# cafereg2.net
KiCad netlist of a schematic drawn in EAGLE
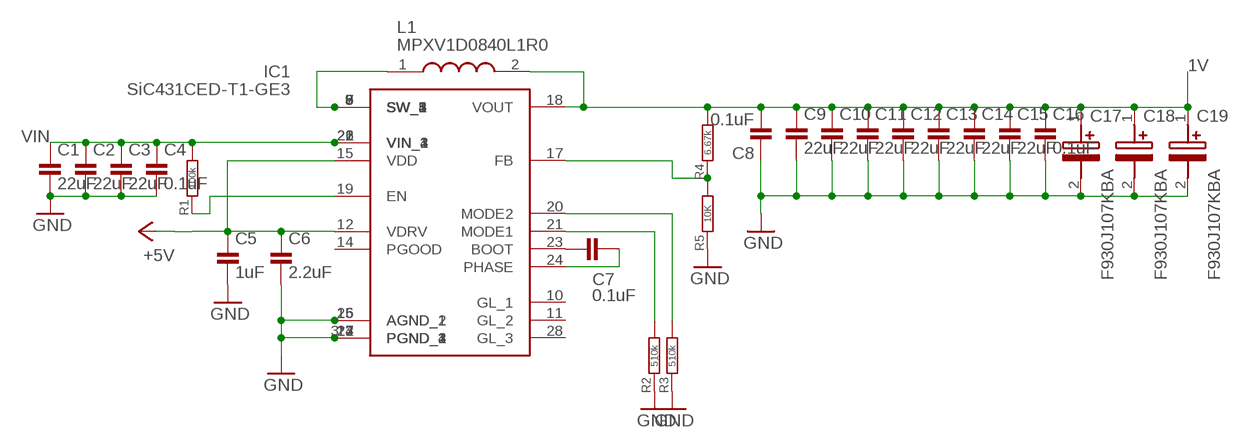
[diagram p0: schematic, sheet 1]
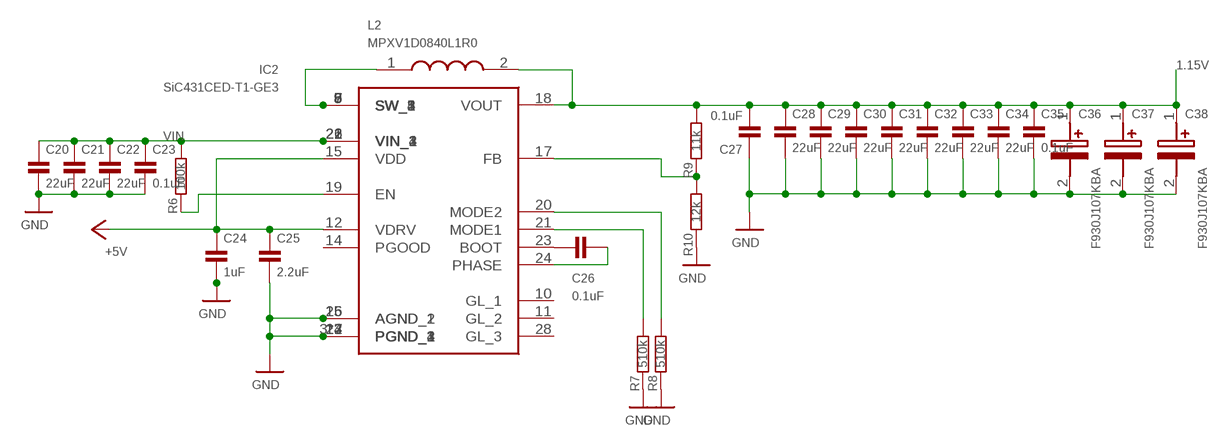
[diagram p1: schematic, sheet 2]
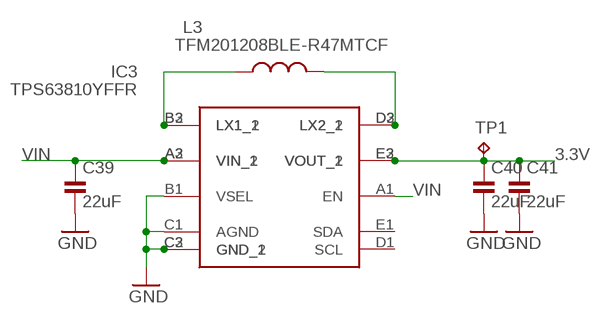
[diagram p2: schematic, sheet 3]
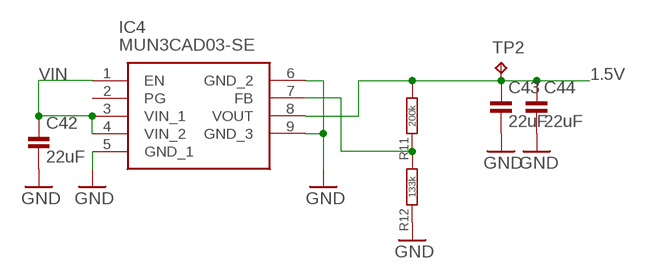
[diagram p3: schematic, sheet 4]
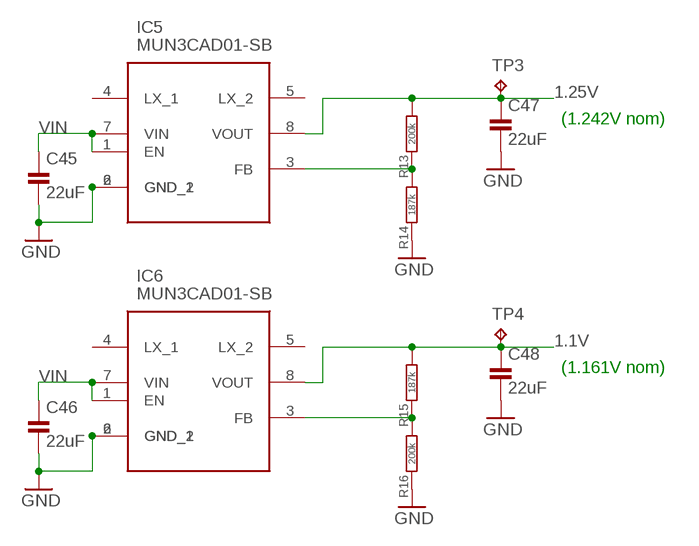
[diagram p4: schematic, sheet 5]
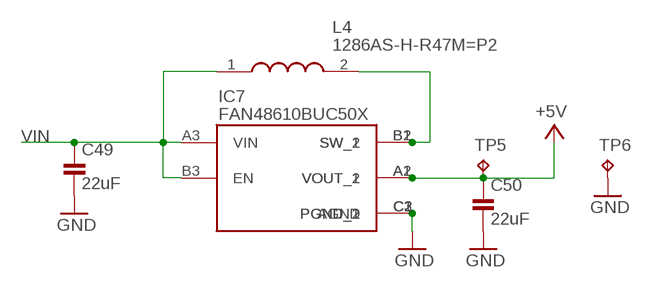
[diagram p5: schematic, sheet 6]

(export (version "E")
  (design (tool "Eeschema 10.0.6"))
  (components
    (comp (ref "C1")
      (value "22uF")
      (footprint "eagle-import:C0603")
      (libsource (lib "eagle-import") (part "C-USC0603"))
    )
    (comp (ref "C2")
      (value "22uF")
      (footprint "eagle-import:C0603")
      (libsource (lib "eagle-import") (part "C-USC0603"))
    )
    (comp (ref "C3")
      (value "22uF")
      (footprint "eagle-import:C0603")
      (libsource (lib "eagle-import") (part "C-USC0603"))
    )
    (comp (ref "C4")
      (value "0.1uF")
      (footprint "eagle-import:C0402")
      (libsource (lib "eagle-import") (part "C-USC0402"))
    )
    (comp (ref "C5")
      (value "1uF")
      (footprint "eagle-import:C0402")
      (libsource (lib "eagle-import") (part "C-USC0402"))
    )
    (comp (ref "C6")
      (value "2.2uF")
      (footprint "eagle-import:C0402")
      (libsource (lib "eagle-import") (part "C-USC0402"))
    )
    (comp (ref "C7")
      (value "0.1uF")
      (footprint "eagle-import:C0402")
      (libsource (lib "eagle-import") (part "C-USC0402"))
    )
    (comp (ref "C8")
      (value "0.1uF")
      (footprint "eagle-import:C0402")
      (libsource (lib "eagle-import") (part "C-USC0402"))
    )
    (comp (ref "C9")
      (value "22uF")
      (footprint "eagle-import:C0603")
      (libsource (lib "eagle-import") (part "C-USC0603"))
    )
    (comp (ref "C10")
      (value "22uF")
      (footprint "eagle-import:C0603")
      (libsource (lib "eagle-import") (part "C-USC0603"))
    )
    (comp (ref "C11")
      (value "22uF")
      (footprint "eagle-import:C0603")
      (libsource (lib "eagle-import") (part "C-USC0603"))
    )
    (comp (ref "C12")
      (value "22uF")
      (footprint "eagle-import:C0603")
      (libsource (lib "eagle-import") (part "C-USC0603"))
    )
    (comp (ref "C13")
      (value "22uF")
      (footprint "eagle-import:C0603")
      (libsource (lib "eagle-import") (part "C-USC0603"))
    )
    (comp (ref "C14")
      (value "22uF")
      (footprint "eagle-import:C0603")
      (libsource (lib "eagle-import") (part "C-USC0603"))
    )
    (comp (ref "C15")
      (value "22uF")
      (footprint "eagle-import:C0603")
      (libsource (lib "eagle-import") (part "C-USC0603"))
    )
    (comp (ref "C16")
      (value "0.1uF")
      (footprint "eagle-import:C0402")
      (libsource (lib "eagle-import") (part "C-USC0402"))
    )
    (comp (ref "C17")
      (value "F930J107KBA")
      (footprint "eagle-import:CAPPM3528X210N")
      (fields (field (name "MOUSER_PART_NUMBER") "647-F930J107KBA"))
      (libsource (lib "eagle-import") (part "F930J107KBA"))
    )
    (comp (ref "C18")
      (value "F930J107KBA")
      (footprint "eagle-import:CAPPM3528X210N")
      (fields (field (name "MOUSER_PART_NUMBER") "647-F930J107KBA"))
      (libsource (lib "eagle-import") (part "F930J107KBA"))
    )
    (comp (ref "C19")
      (value "F930J107KBA")
      (footprint "eagle-import:CAPPM3528X210N")
      (fields (field (name "MOUSER_PART_NUMBER") "647-F930J107KBA"))
      (libsource (lib "eagle-import") (part "F930J107KBA"))
    )
    (comp (ref "IC1")
      (value "SiC431CED-T1-GE3")
      (footprint "eagle-import:SIC431AEDT1GE3")
      (fields
        (field (name "MANUFACTURER_PART_NUMBER") "SiC431AED-T1-GE3")
        (field (name "MOUSER_PART_NUMBER") "78-SIC431AED-T1-GE3")
      )
      (libsource (lib "eagle-import") (part "SIC431AED-T1-GE3"))
    )
    (comp (ref "L1")
      (value "MPXV1D0840L1R0")
      (footprint "eagle-import:INDPM8680X400N")
      (libsource (lib "eagle-import") (part "MPXV1D0840L1R0"))
    )
    (comp (ref "R1")
      (value "100k")
      (footprint "eagle-import:R0402")
      (libsource (lib "eagle-import") (part "R-US_R0402"))
    )
    (comp (ref "R2")
      (value "510k")
      (footprint "eagle-import:R0402")
      (libsource (lib "eagle-import") (part "R-US_R0402"))
    )
    (comp (ref "R3")
      (value "510k")
      (footprint "eagle-import:R0402")
      (libsource (lib "eagle-import") (part "R-US_R0402"))
    )
    (comp (ref "R4")
      (value "6.67k")
      (footprint "eagle-import:R0402")
      (libsource (lib "eagle-import") (part "R-US_R0402"))
    )
    (comp (ref "R5")
      (value "10K")
      (footprint "eagle-import:R0402")
      (libsource (lib "eagle-import") (part "R-US_R0402"))
    )
    (comp (ref "C42")
      (value "22uF")
      (footprint "eagle-import:C0603")
      (libsource (lib "eagle-import") (part "C-USC0603"))
    )
    (comp (ref "C43")
      (value "22uF")
      (footprint "eagle-import:C0603")
      (libsource (lib "eagle-import") (part "C-USC0603"))
    )
    (comp (ref "C44")
      (value "22uF")
      (footprint "eagle-import:C0603")
      (libsource (lib "eagle-import") (part "C-USC0603"))
    )
    (comp (ref "IC4")
      (value "MUN3CAD03-SE")
      (footprint "eagle-import:MUN3CAD03SE")
      (fields (field (name "MOUSER_PART_NUMBER") "108-MUN3CAD03-SE"))
      (libsource (lib "eagle-import") (part "MUN3CAD03-SE"))
    )
    (comp (ref "R11")
      (value "200k")
      (footprint "eagle-import:R0402")
      (libsource (lib "eagle-import") (part "R-US_R0402"))
    )
    (comp (ref "R12")
      (value "133k")
      (footprint "eagle-import:R0402")
      (libsource (lib "eagle-import") (part "R-US_R0402"))
    )
    (comp (ref "TP2")
      (value "TPTP12SQ")
      (footprint "eagle-import:TP12SQ")
      (libsource (lib "eagle-import") (part "TPTP12SQ"))
    )
    (comp (ref "C49")
      (value "22uF")
      (footprint "eagle-import:C0603")
      (libsource (lib "eagle-import") (part "C-USC0603"))
    )
    (comp (ref "C50")
      (value "22uF")
      (footprint "eagle-import:C0603")
      (libsource (lib "eagle-import") (part "C-USC0603"))
    )
    (comp (ref "IC7")
      (value "FAN48610BUC50X")
      (footprint "eagle-import:BGA9C40P3X3_122X122X62")
      (fields (field (name "MOUSER_PART_NUMBER") "512-FAN48610BUC50X"))
      (libsource (lib "eagle-import") (part "FAN48610BUC50X"))
    )
    (comp (ref "L4")
      (value "1286AS-H-R47M=P2")
      (footprint "eagle-import:1286ASH1R0MP2")
      (fields (field (name "MOUSER_PART_NUMBER") "81-1286AS-H-R47MP2"))
      (libsource (lib "eagle-import") (part "1286AS-H-R47M=P2"))
    )
    (comp (ref "TP5")
      (value "TPTP12SQ")
      (footprint "eagle-import:TP12SQ")
      (libsource (lib "eagle-import") (part "TPTP12SQ"))
    )
    (comp (ref "TP6")
      (value "TPTP12SQ")
      (footprint "eagle-import:TP12SQ")
      (libsource (lib "eagle-import") (part "TPTP12SQ"))
    )
    (comp (ref "C45")
      (value "22uF")
      (footprint "eagle-import:C0603")
      (libsource (lib "eagle-import") (part "C-USC0603"))
    )
    (comp (ref "C46")
      (value "22uF")
      (footprint "eagle-import:C0603")
      (libsource (lib "eagle-import") (part "C-USC0603"))
    )
    (comp (ref "C47")
      (value "22uF")
      (footprint "eagle-import:C0603")
      (libsource (lib "eagle-import") (part "C-USC0603"))
    )
    (comp (ref "C48")
      (value "22uF")
      (footprint "eagle-import:C0603")
      (libsource (lib "eagle-import") (part "C-USC0603"))
    )
    (comp (ref "IC5")
      (value "MUN3CAD01-SB")
      (footprint "eagle-import:MUN3CAD01SB")
      (libsource (lib "eagle-import") (part "MUN3CAD01-SB"))
    )
    (comp (ref "IC6")
      (value "MUN3CAD01-SB")
      (footprint "eagle-import:MUN3CAD01SB")
      (libsource (lib "eagle-import") (part "MUN3CAD01-SB"))
    )
    (comp (ref "R13")
      (value "200k")
      (footprint "eagle-import:R0402")
      (libsource (lib "eagle-import") (part "R-US_R0402"))
    )
    (comp (ref "R14")
      (value "187k")
      (footprint "eagle-import:R0402")
      (libsource (lib "eagle-import") (part "R-US_R0402"))
    )
    (comp (ref "R15")
      (value "187k")
      (footprint "eagle-import:R0402")
      (libsource (lib "eagle-import") (part "R-US_R0402"))
    )
    (comp (ref "R16")
      (value "200k")
      (footprint "eagle-import:R0402")
      (libsource (lib "eagle-import") (part "R-US_R0402"))
    )
    (comp (ref "TP3")
      (value "TPTP12SQ")
      (footprint "eagle-import:TP12SQ")
      (libsource (lib "eagle-import") (part "TPTP12SQ"))
    )
    (comp (ref "TP4")
      (value "TPTP12SQ")
      (footprint "eagle-import:TP12SQ")
      (libsource (lib "eagle-import") (part "TPTP12SQ"))
    )
    (comp (ref "C20")
      (value "22uF")
      (footprint "eagle-import:C0603")
      (libsource (lib "eagle-import") (part "C-USC0603"))
    )
    (comp (ref "C21")
      (value "22uF")
      (footprint "eagle-import:C0603")
      (libsource (lib "eagle-import") (part "C-USC0603"))
    )
    (comp (ref "C22")
      (value "22uF")
      (footprint "eagle-import:C0603")
      (libsource (lib "eagle-import") (part "C-USC0603"))
    )
    (comp (ref "C23")
      (value "0.1uF")
      (footprint "eagle-import:C0402")
      (libsource (lib "eagle-import") (part "C-USC0402"))
    )
    (comp (ref "C24")
      (value "1uF")
      (footprint "eagle-import:C0402")
      (libsource (lib "eagle-import") (part "C-USC0402"))
    )
    (comp (ref "C25")
      (value "2.2uF")
      (footprint "eagle-import:C0402")
      (libsource (lib "eagle-import") (part "C-USC0402"))
    )
    (comp (ref "C26")
      (value "0.1uF")
      (footprint "eagle-import:C0402")
      (libsource (lib "eagle-import") (part "C-USC0402"))
    )
    (comp (ref "C27")
      (value "0.1uF")
      (footprint "eagle-import:C0402")
      (libsource (lib "eagle-import") (part "C-USC0402"))
    )
    (comp (ref "C28")
      (value "22uF")
      (footprint "eagle-import:C0603")
      (libsource (lib "eagle-import") (part "C-USC0603"))
    )
    (comp (ref "C29")
      (value "22uF")
      (footprint "eagle-import:C0603")
      (libsource (lib "eagle-import") (part "C-USC0603"))
    )
    (comp (ref "C30")
      (value "22uF")
      (footprint "eagle-import:C0603")
      (libsource (lib "eagle-import") (part "C-USC0603"))
    )
    (comp (ref "C31")
      (value "22uF")
      (footprint "eagle-import:C0603")
      (libsource (lib "eagle-import") (part "C-USC0603"))
    )
    (comp (ref "C32")
      (value "22uF")
      (footprint "eagle-import:C0603")
      (libsource (lib "eagle-import") (part "C-USC0603"))
    )
    (comp (ref "C33")
      (value "22uF")
      (footprint "eagle-import:C0603")
      (libsource (lib "eagle-import") (part "C-USC0603"))
    )
    (comp (ref "C34")
      (value "22uF")
      (footprint "eagle-import:C0603")
      (libsource (lib "eagle-import") (part "C-USC0603"))
    )
    (comp (ref "C35")
      (value "0.1uF")
      (footprint "eagle-import:C0402")
      (libsource (lib "eagle-import") (part "C-USC0402"))
    )
    (comp (ref "C36")
      (value "F930J107KBA")
      (footprint "eagle-import:CAPPM3528X210N")
      (fields (field (name "MOUSER_PART_NUMBER") "647-F930J107KBA"))
      (libsource (lib "eagle-import") (part "F930J107KBA"))
    )
    (comp (ref "C37")
      (value "F930J107KBA")
      (footprint "eagle-import:CAPPM3528X210N")
      (fields (field (name "MOUSER_PART_NUMBER") "647-F930J107KBA"))
      (libsource (lib "eagle-import") (part "F930J107KBA"))
    )
    (comp (ref "C38")
      (value "F930J107KBA")
      (footprint "eagle-import:CAPPM3528X210N")
      (fields (field (name "MOUSER_PART_NUMBER") "647-F930J107KBA"))
      (libsource (lib "eagle-import") (part "F930J107KBA"))
    )
    (comp (ref "IC2")
      (value "SiC431CED-T1-GE3")
      (footprint "eagle-import:SIC431AEDT1GE3")
      (fields
        (field (name "MANUFACTURER_PART_NUMBER") "SiC431AED-T1-GE3")
        (field (name "MOUSER_PART_NUMBER") "78-SIC431AED-T1-GE3")
      )
      (libsource (lib "eagle-import") (part "SIC431AED-T1-GE3"))
    )
    (comp (ref "L2")
      (value "MPXV1D0840L1R0")
      (footprint "eagle-import:INDPM8680X400N")
      (libsource (lib "eagle-import") (part "MPXV1D0840L1R0"))
    )
    (comp (ref "R6")
      (value "100k")
      (footprint "eagle-import:R0402")
      (libsource (lib "eagle-import") (part "R-US_R0402"))
    )
    (comp (ref "R7")
      (value "510k")
      (footprint "eagle-import:R0402")
      (libsource (lib "eagle-import") (part "R-US_R0402"))
    )
    (comp (ref "R8")
      (value "510k")
      (footprint "eagle-import:R0402")
      (libsource (lib "eagle-import") (part "R-US_R0402"))
    )
    (comp (ref "R9")
      (value "11k")
      (footprint "eagle-import:R0402")
      (libsource (lib "eagle-import") (part "R-US_R0402"))
    )
    (comp (ref "R10")
      (value "12k")
      (footprint "eagle-import:R0402")
      (libsource (lib "eagle-import") (part "R-US_R0402"))
    )
    (comp (ref "C39")
      (value "22uF")
      (footprint "eagle-import:C0603")
      (libsource (lib "eagle-import") (part "C-USC0603"))
    )
    (comp (ref "C40")
      (value "22uF")
      (footprint "eagle-import:C0603")
      (libsource (lib "eagle-import") (part "C-USC0603"))
    )
    (comp (ref "C41")
      (value "22uF")
      (footprint "eagle-import:C0603")
      (libsource (lib "eagle-import") (part "C-USC0603"))
    )
    (comp (ref "IC3")
      (value "TPS63810YFFR")
      (footprint "eagle-import:BGA15C40P3X5_134X226X62")
      (fields (field (name "MOUSER_PART_NUMBER") "595-TPS63810YFFR"))
      (libsource (lib "eagle-import") (part "TPS63810YFFR"))
    )
    (comp (ref "L3")
      (value "TFM201208BLE-R47MTCF")
      (footprint "eagle-import:INDC2009X120")
      (libsource (lib "eagle-import") (part "LCHIP-0805(2012-METRIC)_"))
    )
    (comp (ref "TP1")
      (value "TPTP12SQ")
      (footprint "eagle-import:TP12SQ")
      (libsource (lib "eagle-import") (part "TPTP12SQ"))
    )
  )
  (nets
    (net (code "1") (name "+5V") (class "Default")
      (node (ref "C24") (pin "1") (pinfunction "1_1") (pintype "passive"))
      (node (ref "C25") (pin "1") (pinfunction "1_1") (pintype "passive"))
      (node (ref "C5") (pin "1") (pinfunction "1_1") (pintype "passive"))
      (node (ref "C50") (pin "1") (pinfunction "1_1") (pintype "passive"))
      (node (ref "C6") (pin "1") (pinfunction "1_1") (pintype "passive"))
      (node (ref "IC1") (pin "12") (pinfunction "VDRV_12") (pintype "bidirectional"))
      (node (ref "IC1") (pin "15") (pinfunction "VDD_15") (pintype "bidirectional"))
      (node (ref "IC2") (pin "12") (pinfunction "VDRV_12") (pintype "bidirectional"))
      (node (ref "IC2") (pin "15") (pinfunction "VDD_15") (pintype "bidirectional"))
      (node (ref "IC7") (pin "A1") (pinfunction "VOUT_1_A1") (pintype "bidirectional"))
      (node (ref "IC7") (pin "A2") (pinfunction "VOUT_2_A2") (pintype "bidirectional"))
      (node (ref "TP5") (pin "TP") (pinfunction "TP_TP") (pintype "input"))
    )
    (net (code "2") (name "1.1V") (class "Default")
      (node (ref "C48") (pin "1") (pinfunction "1_1") (pintype "passive"))
      (node (ref "IC6") (pin "8") (pinfunction "VOUT_8") (pintype "bidirectional"))
      (node (ref "R15") (pin "2") (pinfunction "2_2") (pintype "passive"))
      (node (ref "TP4") (pin "TP") (pinfunction "TP_TP") (pintype "input"))
    )
    (net (code "3") (name "1.5V") (class "Default")
      (node (ref "C43") (pin "1") (pinfunction "1_1") (pintype "passive"))
      (node (ref "C44") (pin "1") (pinfunction "1_1") (pintype "passive"))
      (node (ref "IC4") (pin "8") (pinfunction "VOUT_8") (pintype "bidirectional"))
      (node (ref "R11") (pin "2") (pinfunction "2_2") (pintype "passive"))
      (node (ref "TP2") (pin "TP") (pinfunction "TP_TP") (pintype "input"))
    )
    (net (code "4") (name "1.15V") (class "Default")
      (node (ref "C27") (pin "2") (pinfunction "2_2") (pintype "passive"))
      (node (ref "C28") (pin "1") (pinfunction "1_1") (pintype "passive"))
      (node (ref "C29") (pin "1") (pinfunction "1_1") (pintype "passive"))
      (node (ref "C30") (pin "1") (pinfunction "1_1") (pintype "passive"))
      (node (ref "C31") (pin "1") (pinfunction "1_1") (pintype "passive"))
      (node (ref "C32") (pin "1") (pinfunction "1_1") (pintype "passive"))
      (node (ref "C33") (pin "1") (pinfunction "1_1") (pintype "passive"))
      (node (ref "C34") (pin "1") (pinfunction "1_1") (pintype "passive"))
      (node (ref "C35") (pin "1") (pinfunction "1_1") (pintype "passive"))
      (node (ref "C36") (pin "1") (pinfunction "+_1") (pintype "bidirectional"))
      (node (ref "C37") (pin "1") (pinfunction "+_1") (pintype "bidirectional"))
      (node (ref "C38") (pin "1") (pinfunction "+_1") (pintype "bidirectional"))
      (node (ref "IC2") (pin "18") (pinfunction "VOUT_18") (pintype "bidirectional"))
      (node (ref "L2") (pin "2") (pinfunction "2_2") (pintype "bidirectional"))
      (node (ref "R9") (pin "2") (pinfunction "2_2") (pintype "passive"))
    )
    (net (code "5") (name "1.25V") (class "Default")
      (node (ref "C47") (pin "1") (pinfunction "1_1") (pintype "passive"))
      (node (ref "IC5") (pin "8") (pinfunction "VOUT_8") (pintype "bidirectional"))
      (node (ref "R13") (pin "2") (pinfunction "2_2") (pintype "passive"))
      (node (ref "TP3") (pin "TP") (pinfunction "TP_TP") (pintype "input"))
    )
    (net (code "6") (name "1V") (class "Default")
      (node (ref "C10") (pin "1") (pinfunction "1_1") (pintype "passive"))
      (node (ref "C11") (pin "1") (pinfunction "1_1") (pintype "passive"))
      (node (ref "C12") (pin "1") (pinfunction "1_1") (pintype "passive"))
      (node (ref "C13") (pin "1") (pinfunction "1_1") (pintype "passive"))
      (node (ref "C14") (pin "1") (pinfunction "1_1") (pintype "passive"))
      (node (ref "C15") (pin "1") (pinfunction "1_1") (pintype "passive"))
      (node (ref "C16") (pin "1") (pinfunction "1_1") (pintype "passive"))
      (node (ref "C17") (pin "1") (pinfunction "+_1") (pintype "bidirectional"))
      (node (ref "C18") (pin "1") (pinfunction "+_1") (pintype "bidirectional"))
      (node (ref "C19") (pin "1") (pinfunction "+_1") (pintype "bidirectional"))
      (node (ref "C8") (pin "2") (pinfunction "2_2") (pintype "passive"))
      (node (ref "C9") (pin "1") (pinfunction "1_1") (pintype "passive"))
      (node (ref "IC1") (pin "18") (pinfunction "VOUT_18") (pintype "bidirectional"))
      (node (ref "L1") (pin "2") (pinfunction "2_2") (pintype "bidirectional"))
      (node (ref "R4") (pin "2") (pinfunction "2_2") (pintype "passive"))
    )
    (net (code "7") (name "3.3V") (class "Default")
      (node (ref "C40") (pin "1") (pinfunction "1_1") (pintype "passive"))
      (node (ref "C41") (pin "1") (pinfunction "1_1") (pintype "passive"))
      (node (ref "IC3") (pin "E2") (pinfunction "VOUT_1_E2") (pintype "bidirectional"))
      (node (ref "IC3") (pin "E3") (pinfunction "VOUT_2_E3") (pintype "bidirectional"))
      (node (ref "TP1") (pin "TP") (pinfunction "TP_TP") (pintype "input"))
    )
    (net (code "8") (name "GND") (class "Default")
      (node (ref "C1") (pin "2") (pinfunction "2_2") (pintype "passive"))
      (node (ref "C10") (pin "2") (pinfunction "2_2") (pintype "passive"))
      (node (ref "C11") (pin "2") (pinfunction "2_2") (pintype "passive"))
      (node (ref "C12") (pin "2") (pinfunction "2_2") (pintype "passive"))
      (node (ref "C13") (pin "2") (pinfunction "2_2") (pintype "passive"))
      (node (ref "C14") (pin "2") (pinfunction "2_2") (pintype "passive"))
      (node (ref "C15") (pin "2") (pinfunction "2_2") (pintype "passive"))
      (node (ref "C16") (pin "2") (pinfunction "2_2") (pintype "passive"))
      (node (ref "C17") (pin "2") (pinfunction "-_2") (pintype "bidirectional"))
      (node (ref "C18") (pin "2") (pinfunction "-_2") (pintype "bidirectional"))
      (node (ref "C19") (pin "2") (pinfunction "-_2") (pintype "bidirectional"))
      (node (ref "C2") (pin "2") (pinfunction "2_2") (pintype "passive"))
      (node (ref "C20") (pin "2") (pinfunction "2_2") (pintype "passive"))
      (node (ref "C21") (pin "2") (pinfunction "2_2") (pintype "passive"))
      (node (ref "C22") (pin "2") (pinfunction "2_2") (pintype "passive"))
      (node (ref "C23") (pin "2") (pinfunction "2_2") (pintype "passive"))
      (node (ref "C24") (pin "2") (pinfunction "2_2") (pintype "passive"))
      (node (ref "C25") (pin "2") (pinfunction "2_2") (pintype "passive"))
      (node (ref "C27") (pin "1") (pinfunction "1_1") (pintype "passive"))
      (node (ref "C28") (pin "2") (pinfunction "2_2") (pintype "passive"))
      (node (ref "C29") (pin "2") (pinfunction "2_2") (pintype "passive"))
      (node (ref "C3") (pin "2") (pinfunction "2_2") (pintype "passive"))
      (node (ref "C30") (pin "2") (pinfunction "2_2") (pintype "passive"))
      (node (ref "C31") (pin "2") (pinfunction "2_2") (pintype "passive"))
      (node (ref "C32") (pin "2") (pinfunction "2_2") (pintype "passive"))
      (node (ref "C33") (pin "2") (pinfunction "2_2") (pintype "passive"))
      (node (ref "C34") (pin "2") (pinfunction "2_2") (pintype "passive"))
      (node (ref "C35") (pin "2") (pinfunction "2_2") (pintype "passive"))
      (node (ref "C36") (pin "2") (pinfunction "-_2") (pintype "bidirectional"))
      (node (ref "C37") (pin "2") (pinfunction "-_2") (pintype "bidirectional"))
      (node (ref "C38") (pin "2") (pinfunction "-_2") (pintype "bidirectional"))
      (node (ref "C39") (pin "2") (pinfunction "2_2") (pintype "passive"))
      (node (ref "C4") (pin "2") (pinfunction "2_2") (pintype "passive"))
      (node (ref "C40") (pin "2") (pinfunction "2_2") (pintype "passive"))
      (node (ref "C41") (pin "2") (pinfunction "2_2") (pintype "passive"))
      (node (ref "C42") (pin "2") (pinfunction "2_2") (pintype "passive"))
      (node (ref "C43") (pin "2") (pinfunction "2_2") (pintype "passive"))
      (node (ref "C44") (pin "2") (pinfunction "2_2") (pintype "passive"))
      (node (ref "C45") (pin "2") (pinfunction "2_2") (pintype "passive"))
      (node (ref "C46") (pin "2") (pinfunction "2_2") (pintype "passive"))
      (node (ref "C47") (pin "2") (pinfunction "2_2") (pintype "passive"))
      (node (ref "C48") (pin "2") (pinfunction "2_2") (pintype "passive"))
      (node (ref "C49") (pin "2") (pinfunction "2_2") (pintype "passive"))
      (node (ref "C5") (pin "2") (pinfunction "2_2") (pintype "passive"))
      (node (ref "C50") (pin "2") (pinfunction "2_2") (pintype "passive"))
      (node (ref "C6") (pin "2") (pinfunction "2_2") (pintype "passive"))
      (node (ref "C8") (pin "1") (pinfunction "1_1") (pintype "passive"))
      (node (ref "C9") (pin "2") (pinfunction "2_2") (pintype "passive"))
      (node (ref "IC1") (pin "13") (pinfunction "PGND_3_13") (pintype "bidirectional"))
      (node (ref "IC1") (pin "16") (pinfunction "AGND_1_16") (pintype "bidirectional"))
      (node (ref "IC1") (pin "25") (pinfunction "AGND_2_25") (pintype "bidirectional"))
      (node (ref "IC1") (pin "27") (pinfunction "PGND_4_27") (pintype "bidirectional"))
      (node (ref "IC1") (pin "29") (pinfunction "PGND_1_29") (pintype "bidirectional"))
      (node (ref "IC1") (pin "3") (pinfunction "PGND_1_3") (pintype "bidirectional"))
      (node (ref "IC1") (pin "4") (pinfunction "PGND_2_4") (pintype "bidirectional"))
      (node (ref "IC2") (pin "13") (pinfunction "PGND_3_13") (pintype "bidirectional"))
      (node (ref "IC2") (pin "16") (pinfunction "AGND_1_16") (pintype "bidirectional"))
      (node (ref "IC2") (pin "25") (pinfunction "AGND_2_25") (pintype "bidirectional"))
      (node (ref "IC2") (pin "27") (pinfunction "PGND_4_27") (pintype "bidirectional"))
      (node (ref "IC2") (pin "29") (pinfunction "PGND_1_29") (pintype "bidirectional"))
      (node (ref "IC2") (pin "3") (pinfunction "PGND_1_3") (pintype "bidirectional"))
      (node (ref "IC2") (pin "4") (pinfunction "PGND_2_4") (pintype "bidirectional"))
      (node (ref "IC3") (pin "B1") (pinfunction "VSEL_B1") (pintype "bidirectional"))
      (node (ref "IC3") (pin "C1") (pinfunction "AGND_C1") (pintype "bidirectional"))
      (node (ref "IC3") (pin "C2") (pinfunction "GND_1_C2") (pintype "bidirectional"))
      (node (ref "IC3") (pin "C3") (pinfunction "GND_2_C3") (pintype "bidirectional"))
      (node (ref "IC4") (pin "5") (pinfunction "GND_1_5") (pintype "bidirectional"))
      (node (ref "IC4") (pin "6") (pinfunction "GND_2_6") (pintype "bidirectional"))
      (node (ref "IC4") (pin "9") (pinfunction "GND_3_9") (pintype "bidirectional"))
      (node (ref "IC5") (pin "2") (pinfunction "GND_1_2") (pintype "bidirectional"))
      (node (ref "IC5") (pin "6") (pinfunction "GND_2_6") (pintype "bidirectional"))
      (node (ref "IC6") (pin "2") (pinfunction "GND_1_2") (pintype "bidirectional"))
      (node (ref "IC6") (pin "6") (pinfunction "GND_2_6") (pintype "bidirectional"))
      (node (ref "IC7") (pin "C1") (pinfunction "PGND_1_C1") (pintype "bidirectional"))
      (node (ref "IC7") (pin "C2") (pinfunction "PGND_2_C2") (pintype "bidirectional"))
      (node (ref "IC7") (pin "C3") (pinfunction "AGND_C3") (pintype "bidirectional"))
      (node (ref "R10") (pin "1") (pinfunction "1_1") (pintype "passive"))
      (node (ref "R12") (pin "1") (pinfunction "1_1") (pintype "passive"))
      (node (ref "R14") (pin "1") (pinfunction "1_1") (pintype "passive"))
      (node (ref "R16") (pin "1") (pinfunction "1_1") (pintype "passive"))
      (node (ref "R2") (pin "1") (pinfunction "1_1") (pintype "passive"))
      (node (ref "R3") (pin "1") (pinfunction "1_1") (pintype "passive"))
      (node (ref "R5") (pin "1") (pinfunction "1_1") (pintype "passive"))
      (node (ref "R7") (pin "1") (pinfunction "1_1") (pintype "passive"))
      (node (ref "R8") (pin "1") (pinfunction "1_1") (pintype "passive"))
      (node (ref "TP6") (pin "TP") (pinfunction "TP_TP") (pintype "input"))
    )
    (net (code "9") (name "Net-(IC1-BOOT)") (class "Default")
      (node (ref "C7") (pin "1") (pinfunction "1_1") (pintype "passive"))
      (node (ref "IC1") (pin "23") (pinfunction "BOOT_23") (pintype "bidirectional"))
    )
    (net (code "10") (name "Net-(IC1-EN)") (class "Default")
      (node (ref "IC1") (pin "19") (pinfunction "EN_19") (pintype "bidirectional"))
      (node (ref "R1") (pin "1") (pinfunction "1_1") (pintype "passive"))
    )
    (net (code "11") (name "Net-(IC1-FB)") (class "Default")
      (node (ref "IC1") (pin "17") (pinfunction "FB_17") (pintype "bidirectional"))
      (node (ref "R4") (pin "1") (pinfunction "1_1") (pintype "passive"))
      (node (ref "R5") (pin "2") (pinfunction "2_2") (pintype "passive"))
    )
    (net (code "12") (name "Net-(IC1-MODE1)") (class "Default")
      (node (ref "IC1") (pin "21") (pinfunction "MODE1_21") (pintype "bidirectional"))
      (node (ref "R2") (pin "2") (pinfunction "2_2") (pintype "passive"))
    )
    (net (code "13") (name "Net-(IC1-MODE2)") (class "Default")
      (node (ref "IC1") (pin "20") (pinfunction "MODE2_20") (pintype "bidirectional"))
      (node (ref "R3") (pin "2") (pinfunction "2_2") (pintype "passive"))
    )
    (net (code "14") (name "Net-(IC1-PHASE)") (class "Default")
      (node (ref "C7") (pin "2") (pinfunction "2_2") (pintype "passive"))
      (node (ref "IC1") (pin "24") (pinfunction "PHASE_24") (pintype "bidirectional"))
    )
    (net (code "15") (name "Net-(IC1-SW_1)") (class "Default")
      (node (ref "IC1") (pin "5") (pinfunction "SW_1_5") (pintype "bidirectional"))
      (node (ref "IC1") (pin "6") (pinfunction "SW_2_6") (pintype "bidirectional"))
      (node (ref "IC1") (pin "7") (pinfunction "SW_3_7") (pintype "bidirectional"))
      (node (ref "IC1") (pin "8") (pinfunction "SW_4_8") (pintype "bidirectional"))
      (node (ref "IC1") (pin "9") (pinfunction "SW_5_9") (pintype "bidirectional"))
      (node (ref "L1") (pin "1") (pinfunction "1_1") (pintype "bidirectional"))
    )
    (net (code "16") (name "Net-(IC2-BOOT)") (class "Default")
      (node (ref "C26") (pin "1") (pinfunction "1_1") (pintype "passive"))
      (node (ref "IC2") (pin "23") (pinfunction "BOOT_23") (pintype "bidirectional"))
    )
    (net (code "17") (name "Net-(IC2-EN)") (class "Default")
      (node (ref "IC2") (pin "19") (pinfunction "EN_19") (pintype "bidirectional"))
      (node (ref "R6") (pin "1") (pinfunction "1_1") (pintype "passive"))
    )
    (net (code "18") (name "Net-(IC2-FB)") (class "Default")
      (node (ref "IC2") (pin "17") (pinfunction "FB_17") (pintype "bidirectional"))
      (node (ref "R10") (pin "2") (pinfunction "2_2") (pintype "passive"))
      (node (ref "R9") (pin "1") (pinfunction "1_1") (pintype "passive"))
    )
    (net (code "19") (name "Net-(IC2-MODE1)") (class "Default")
      (node (ref "IC2") (pin "21") (pinfunction "MODE1_21") (pintype "bidirectional"))
      (node (ref "R7") (pin "2") (pinfunction "2_2") (pintype "passive"))
    )
    (net (code "20") (name "Net-(IC2-MODE2)") (class "Default")
      (node (ref "IC2") (pin "20") (pinfunction "MODE2_20") (pintype "bidirectional"))
      (node (ref "R8") (pin "2") (pinfunction "2_2") (pintype "passive"))
    )
    (net (code "21") (name "Net-(IC2-PHASE)") (class "Default")
      (node (ref "C26") (pin "2") (pinfunction "2_2") (pintype "passive"))
      (node (ref "IC2") (pin "24") (pinfunction "PHASE_24") (pintype "bidirectional"))
    )
    (net (code "22") (name "Net-(IC2-SW_1)") (class "Default")
      (node (ref "IC2") (pin "5") (pinfunction "SW_1_5") (pintype "bidirectional"))
      (node (ref "IC2") (pin "6") (pinfunction "SW_2_6") (pintype "bidirectional"))
      (node (ref "IC2") (pin "7") (pinfunction "SW_3_7") (pintype "bidirectional"))
      (node (ref "IC2") (pin "8") (pinfunction "SW_4_8") (pintype "bidirectional"))
      (node (ref "IC2") (pin "9") (pinfunction "SW_5_9") (pintype "bidirectional"))
      (node (ref "L2") (pin "1") (pinfunction "1_1") (pintype "bidirectional"))
    )
    (net (code "23") (name "Net-(IC3-LX1_1)") (class "Default")
      (node (ref "IC3") (pin "B2") (pinfunction "LX1_1_B2") (pintype "bidirectional"))
      (node (ref "IC3") (pin "B3") (pinfunction "LX1_2_B3") (pintype "bidirectional"))
      (node (ref "L3") (pin "1") (pinfunction "1_1") (pintype "passive"))
    )
    (net (code "24") (name "Net-(IC3-LX2_1)") (class "Default")
      (node (ref "IC3") (pin "D2") (pinfunction "LX2_1_D2") (pintype "bidirectional"))
      (node (ref "IC3") (pin "D3") (pinfunction "LX2_2_D3") (pintype "bidirectional"))
      (node (ref "L3") (pin "2") (pinfunction "2_2") (pintype "passive"))
    )
    (net (code "25") (name "Net-(IC4-FB)") (class "Default")
      (node (ref "IC4") (pin "7") (pinfunction "FB_7") (pintype "bidirectional"))
      (node (ref "R11") (pin "1") (pinfunction "1_1") (pintype "passive"))
      (node (ref "R12") (pin "2") (pinfunction "2_2") (pintype "passive"))
    )
    (net (code "26") (name "Net-(IC5-FB)") (class "Default")
      (node (ref "IC5") (pin "3") (pinfunction "FB_3") (pintype "bidirectional"))
      (node (ref "R13") (pin "1") (pinfunction "1_1") (pintype "passive"))
      (node (ref "R14") (pin "2") (pinfunction "2_2") (pintype "passive"))
    )
    (net (code "27") (name "Net-(IC6-FB)") (class "Default")
      (node (ref "IC6") (pin "3") (pinfunction "FB_3") (pintype "bidirectional"))
      (node (ref "R15") (pin "1") (pinfunction "1_1") (pintype "passive"))
      (node (ref "R16") (pin "2") (pinfunction "2_2") (pintype "passive"))
    )
    (net (code "28") (name "Net-(IC7-SW_1)") (class "Default")
      (node (ref "IC7") (pin "B1") (pinfunction "SW_1_B1") (pintype "bidirectional"))
      (node (ref "IC7") (pin "B2") (pinfunction "SW_2_B2") (pintype "bidirectional"))
      (node (ref "L4") (pin "2") (pinfunction "2_2") (pintype "bidirectional"))
    )
    (net (code "29") (name "VIN") (class "Default")
      (node (ref "C1") (pin "1") (pinfunction "1_1") (pintype "passive"))
      (node (ref "C2") (pin "1") (pinfunction "1_1") (pintype "passive"))
      (node (ref "C20") (pin "1") (pinfunction "1_1") (pintype "passive"))
      (node (ref "C21") (pin "1") (pinfunction "1_1") (pintype "passive"))
      (node (ref "C22") (pin "1") (pinfunction "1_1") (pintype "passive"))
      (node (ref "C23") (pin "1") (pinfunction "1_1") (pintype "passive"))
      (node (ref "C3") (pin "1") (pinfunction "1_1") (pintype "passive"))
      (node (ref "C39") (pin "1") (pinfunction "1_1") (pintype "passive"))
      (node (ref "C4") (pin "1") (pinfunction "1_1") (pintype "passive"))
      (node (ref "C42") (pin "1") (pinfunction "1_1") (pintype "passive"))
      (node (ref "C45") (pin "1") (pinfunction "1_1") (pintype "passive"))
      (node (ref "C46") (pin "1") (pinfunction "1_1") (pintype "passive"))
      (node (ref "C49") (pin "1") (pinfunction "1_1") (pintype "passive"))
      (node (ref "IC1") (pin "1") (pinfunction "VIN_1_1") (pintype "bidirectional"))
      (node (ref "IC1") (pin "2") (pinfunction "VIN_2_2") (pintype "bidirectional"))
      (node (ref "IC1") (pin "22") (pinfunction "VIN_3_22") (pintype "bidirectional"))
      (node (ref "IC1") (pin "26") (pinfunction "VIN_4_26") (pintype "bidirectional"))
      (node (ref "IC2") (pin "1") (pinfunction "VIN_1_1") (pintype "bidirectional"))
      (node (ref "IC2") (pin "2") (pinfunction "VIN_2_2") (pintype "bidirectional"))
      (node (ref "IC2") (pin "22") (pinfunction "VIN_3_22") (pintype "bidirectional"))
      (node (ref "IC2") (pin "26") (pinfunction "VIN_4_26") (pintype "bidirectional"))
      (node (ref "IC3") (pin "A1") (pinfunction "EN_A1") (pintype "bidirectional"))
      (node (ref "IC3") (pin "A2") (pinfunction "VIN_1_A2") (pintype "bidirectional"))
      (node (ref "IC3") (pin "A3") (pinfunction "VIN_2_A3") (pintype "bidirectional"))
      (node (ref "IC4") (pin "1") (pinfunction "EN_1") (pintype "bidirectional"))
      (node (ref "IC4") (pin "3") (pinfunction "VIN_1_3") (pintype "bidirectional"))
      (node (ref "IC4") (pin "4") (pinfunction "VIN_2_4") (pintype "bidirectional"))
      (node (ref "IC5") (pin "1") (pinfunction "EN_1") (pintype "bidirectional"))
      (node (ref "IC5") (pin "7") (pinfunction "VIN_7") (pintype "bidirectional"))
      (node (ref "IC6") (pin "1") (pinfunction "EN_1") (pintype "bidirectional"))
      (node (ref "IC6") (pin "7") (pinfunction "VIN_7") (pintype "bidirectional"))
      (node (ref "IC7") (pin "A3") (pinfunction "VIN_A3") (pintype "bidirectional"))
      (node (ref "IC7") (pin "B3") (pinfunction "EN_B3") (pintype "bidirectional"))
      (node (ref "L4") (pin "1") (pinfunction "1_1") (pintype "bidirectional"))
      (node (ref "R1") (pin "2") (pinfunction "2_2") (pintype "passive"))
      (node (ref "R6") (pin "2") (pinfunction "2_2") (pintype "passive"))
    )
    (net (code "30") (name "unconnected-(IC1-GL_1-Pad10)") (class "Default")
      (node (ref "IC1") (pin "10") (pinfunction "GL_1_10") (pintype "bidirectional"))
    )
    (net (code "31") (name "unconnected-(IC1-GL_2-Pad11)") (class "Default")
      (node (ref "IC1") (pin "11") (pinfunction "GL_2_11") (pintype "bidirectional"))
    )
    (net (code "32") (name "unconnected-(IC1-GL_3-Pad28)") (class "Default")
      (node (ref "IC1") (pin "28") (pinfunction "GL_3_28") (pintype "bidirectional"))
    )
    (net (code "33") (name "unconnected-(IC1-PGOOD-Pad14)") (class "Default")
      (node (ref "IC1") (pin "14") (pinfunction "PGOOD_14") (pintype "bidirectional"))
    )
    (net (code "34") (name "unconnected-(IC2-GL_1-Pad10)") (class "Default")
      (node (ref "IC2") (pin "10") (pinfunction "GL_1_10") (pintype "bidirectional"))
    )
    (net (code "35") (name "unconnected-(IC2-GL_2-Pad11)") (class "Default")
      (node (ref "IC2") (pin "11") (pinfunction "GL_2_11") (pintype "bidirectional"))
    )
    (net (code "36") (name "unconnected-(IC2-GL_3-Pad28)") (class "Default")
      (node (ref "IC2") (pin "28") (pinfunction "GL_3_28") (pintype "bidirectional"))
    )
    (net (code "37") (name "unconnected-(IC2-PGOOD-Pad14)") (class "Default")
      (node (ref "IC2") (pin "14") (pinfunction "PGOOD_14") (pintype "bidirectional"))
    )
    (net (code "38") (name "unconnected-(IC3-SCL-PadD1)") (class "Default")
      (node (ref "IC3") (pin "D1") (pinfunction "SCL_D1") (pintype "bidirectional"))
    )
    (net (code "39") (name "unconnected-(IC3-SDA-PadE1)") (class "Default")
      (node (ref "IC3") (pin "E1") (pinfunction "SDA_E1") (pintype "bidirectional"))
    )
    (net (code "40") (name "unconnected-(IC4-PG-Pad2)") (class "Default")
      (node (ref "IC4") (pin "2") (pinfunction "PG_2") (pintype "bidirectional"))
    )
    (net (code "41") (name "unconnected-(IC5-LX_1-Pad4)") (class "Default")
      (node (ref "IC5") (pin "4") (pinfunction "LX_1_4") (pintype "bidirectional"))
    )
    (net (code "42") (name "unconnected-(IC5-LX_2-Pad5)") (class "Default")
      (node (ref "IC5") (pin "5") (pinfunction "LX_2_5") (pintype "bidirectional"))
    )
    (net (code "43") (name "unconnected-(IC6-LX_1-Pad4)") (class "Default")
      (node (ref "IC6") (pin "4") (pinfunction "LX_1_4") (pintype "bidirectional"))
    )
    (net (code "44") (name "unconnected-(IC6-LX_2-Pad5)") (class "Default")
      (node (ref "IC6") (pin "5") (pinfunction "LX_2_5") (pintype "bidirectional"))
    )
  )
)
